# pingduino.net
KiCad netlist of a schematic drawn in EAGLE
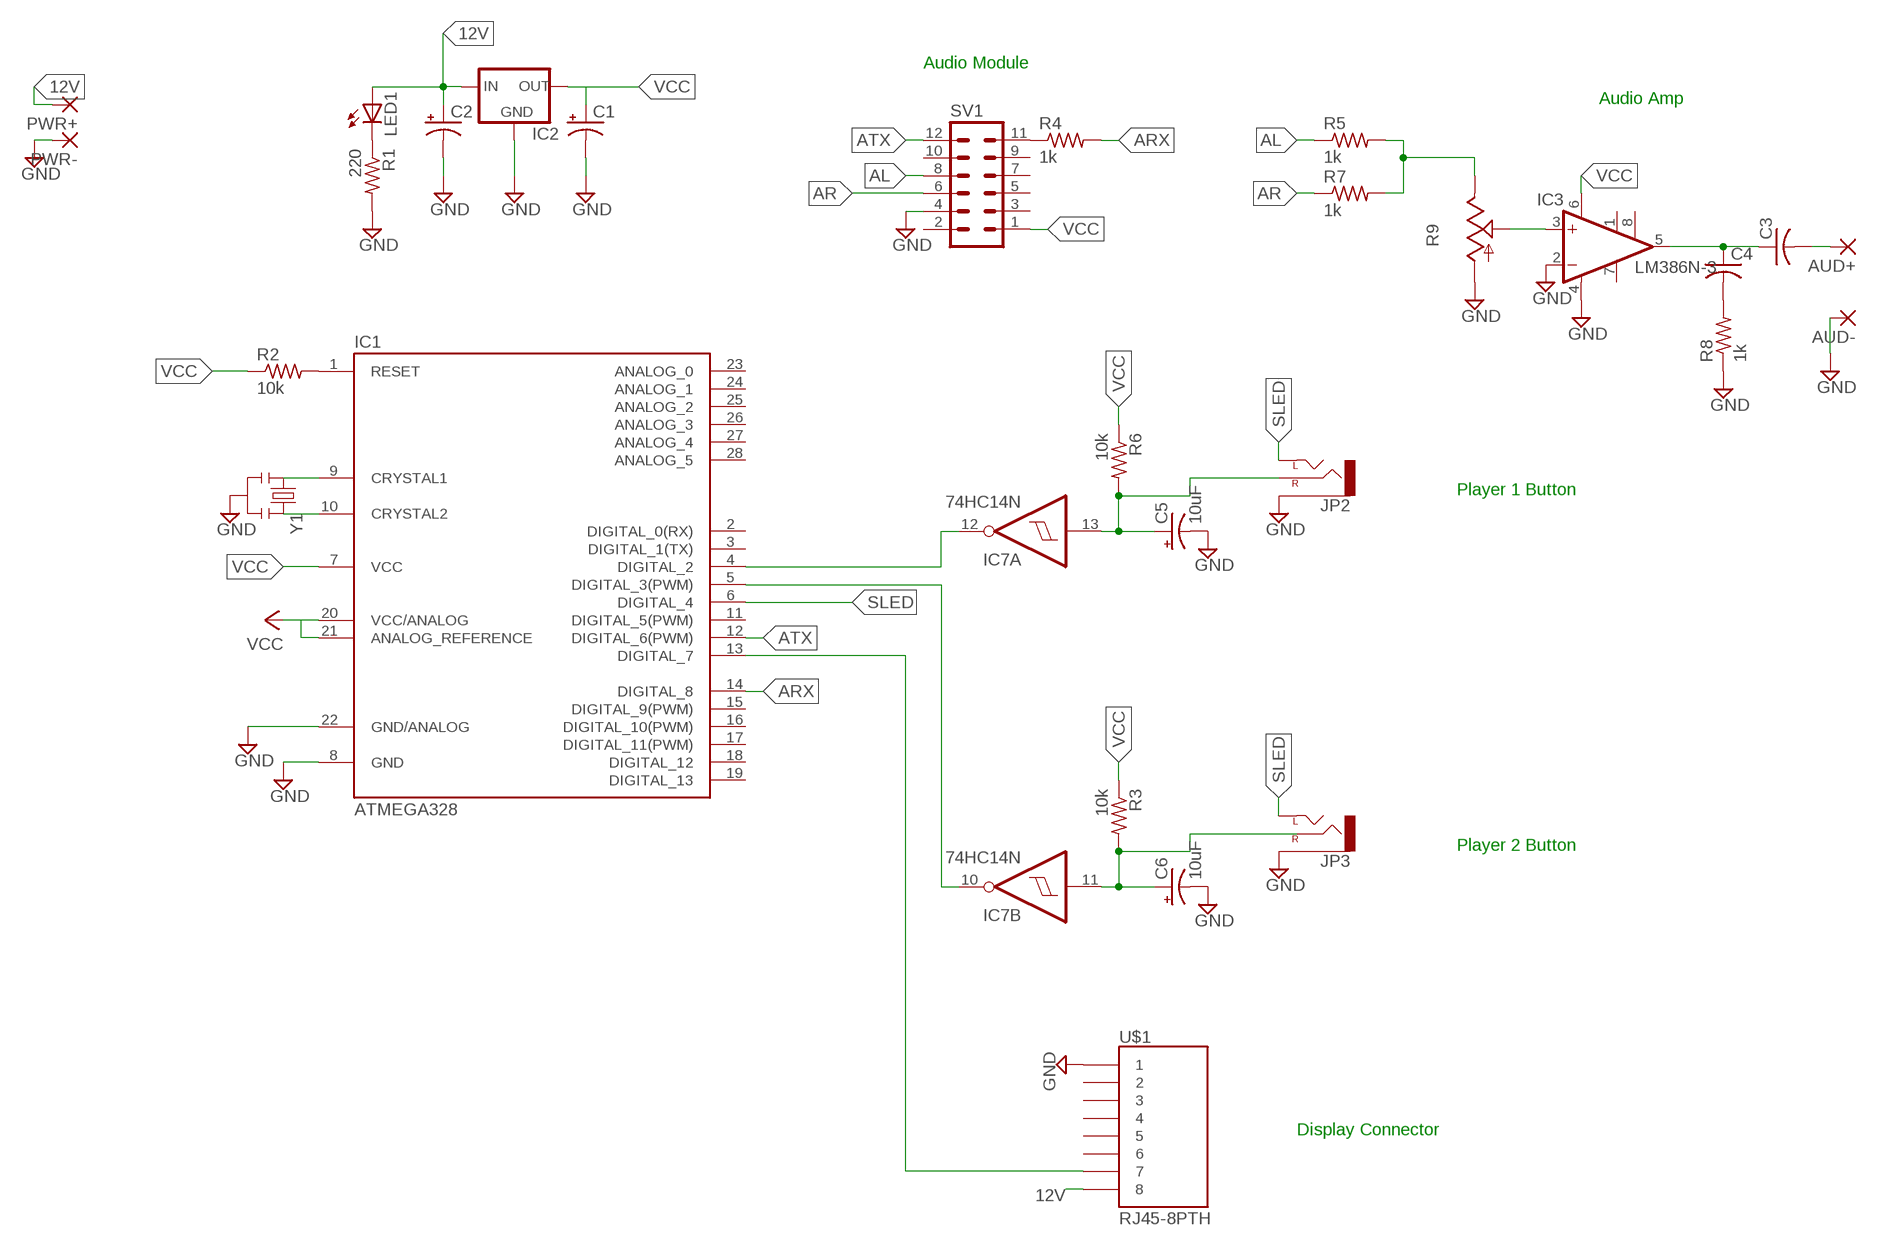
[diagram p0: schematic, sheet 1]

(export (version "E")
  (design (tool "Eeschema 10.0.6"))
  (components
    (comp (ref "AUD+")
      (value "WIREPAD2,15/1,0")
      (footprint "eagle-import:2,15_1,0")
      (libsource (lib "eagle-import") (part "WIREPAD2,15/1,0"))
    )
    (comp (ref "AUD-")
      (value "WIREPAD2,15/1,0")
      (footprint "eagle-import:2,15_1,0")
      (libsource (lib "eagle-import") (part "WIREPAD2,15/1,0"))
    )
    (comp (ref "C1")
      (value "CAP_POLPTH2")
      (footprint "eagle-import:CPOL-RADIAL-10UF-25V")
      (libsource (lib "eagle-import") (part "CAP_POLPTH2"))
    )
    (comp (ref "C2")
      (value "CAP_POLPTH2")
      (footprint "eagle-import:CPOL-RADIAL-10UF-25V")
      (libsource (lib "eagle-import") (part "CAP_POLPTH2"))
    )
    (comp (ref "C3")
      (value "C-US050-024X044")
      (footprint "eagle-import:C050-024X044")
      (libsource (lib "eagle-import") (part "C-US050-024X044"))
    )
    (comp (ref "C4")
      (value "C-US050-024X044")
      (footprint "eagle-import:C050-024X044")
      (libsource (lib "eagle-import") (part "C-US050-024X044"))
    )
    (comp (ref "C5")
      (value "10uF")
      (footprint "eagle-import:CPOL-RADIAL-10UF-25V")
      (libsource (lib "eagle-import") (part "CAP_POLPTH2"))
    )
    (comp (ref "C6")
      (value "10uF")
      (footprint "eagle-import:CPOL-RADIAL-10UF-25V")
      (libsource (lib "eagle-import") (part "CAP_POLPTH2"))
    )
    (comp (ref "IC1")
      (value "ATMEGA328")
      (footprint "eagle-import:DIL28-3")
      (libsource (lib "eagle-import") (part "ATMEGA168-PU"))
    )
    (comp (ref "IC2")
      (value "V_REG_78XX-TO-220")
      (footprint "eagle-import:TO-220-ALT")
      (libsource (lib "eagle-import") (part "V_REG_78XX-TO-220"))
    )
    (comp (ref "IC3")
      (value "LM386N-3")
      (footprint "eagle-import:DIL08")
      (libsource (lib "eagle-import") (part "LM386?-N3"))
    )
    (comp (ref "IC7")
      (value "74HC14N")
      (footprint "eagle-import:DIL14")
      (libsource (lib "eagle-import") (part "7414NHC"))
    )
    (comp (ref "JP2")
      (value "AUDIO-JACKPTH")
      (footprint "eagle-import:AUDIO-JACK")
      (libsource (lib "eagle-import") (part "AUDIO-JACKPTH"))
    )
    (comp (ref "JP3")
      (value "AUDIO-JACKPTH")
      (footprint "eagle-import:AUDIO-JACK")
      (libsource (lib "eagle-import") (part "AUDIO-JACKPTH"))
    )
    (comp (ref "LED1")
      (value "LED3MM")
      (footprint "eagle-import:LED3MM")
      (libsource (lib "eagle-import") (part "LED3MM"))
    )
    (comp (ref "PWR+")
      (value "WIREPAD2,15/1,0")
      (footprint "eagle-import:2,15_1,0")
      (libsource (lib "eagle-import") (part "WIREPAD2,15/1,0"))
    )
    (comp (ref "PWR-")
      (value "WIREPAD2,15/1,0")
      (footprint "eagle-import:2,15_1,0")
      (libsource (lib "eagle-import") (part "WIREPAD2,15/1,0"))
    )
    (comp (ref "R1")
      (value "220")
      (footprint "eagle-import:0204_7")
      (libsource (lib "eagle-import") (part "R-US_0204/7"))
    )
    (comp (ref "R2")
      (value "10k")
      (footprint "eagle-import:0204_7")
      (libsource (lib "eagle-import") (part "R-US_0204/7"))
    )
    (comp (ref "R3")
      (value "10k")
      (footprint "eagle-import:0204_7")
      (libsource (lib "eagle-import") (part "R-US_0204/7"))
    )
    (comp (ref "R4")
      (value "1k")
      (footprint "eagle-import:0204_7")
      (libsource (lib "eagle-import") (part "R-US_0204/7"))
    )
    (comp (ref "R5")
      (value "1k")
      (footprint "eagle-import:0204_7")
      (libsource (lib "eagle-import") (part "R-US_0204/7"))
    )
    (comp (ref "R6")
      (value "10k")
      (footprint "eagle-import:0204_7")
      (libsource (lib "eagle-import") (part "R-US_0204/7"))
    )
    (comp (ref "R7")
      (value "1k")
      (footprint "eagle-import:0204_7")
      (libsource (lib "eagle-import") (part "R-US_0204/7"))
    )
    (comp (ref "R8")
      (value "1k")
      (footprint "eagle-import:0204_7")
      (libsource (lib "eagle-import") (part "R-US_0204/7"))
    )
    (comp (ref "R9")
      (value "TRIM_US-B25U")
      (footprint "eagle-import:B25U")
      (libsource (lib "eagle-import") (part "TRIM_US-B25U"))
    )
    (comp (ref "SV1")
      (value "MA06-2")
      (footprint "eagle-import:MA06-2")
      (libsource (lib "eagle-import") (part "MA06-2"))
    )
    (comp (ref "U$1")
      (value "RJ45-8PTH")
      (footprint "eagle-import:RJ45-8")
      (libsource (lib "eagle-import") (part "RJ45-8PTH"))
    )
    (comp (ref "Y1")
      (value "RESONATORPTH")
      (footprint "eagle-import:RESONATOR-PTH")
      (libsource (lib "eagle-import") (part "RESONATORPTH"))
    )
  )
  (nets
    (net (code "1") (name "12V") (class "Default")
      (node (ref "C2") (pin "1") (pinfunction "+_1") (pintype "passive"))
      (node (ref "IC2") (pin "IN") (pinfunction "IN_IN") (pintype "input"))
      (node (ref "LED1") (pin "A") (pinfunction "A_A") (pintype "passive"))
      (node (ref "PWR+") (pin "1") (pinfunction "P_1") (pintype "passive"))
      (node (ref "U$1") (pin "8") (pinfunction "8_8") (pintype "bidirectional"))
    )
    (net (code "2") (name "AL") (class "Default")
      (node (ref "R5") (pin "1") (pinfunction "1_1") (pintype "passive"))
      (node (ref "SV1") (pin "8") (pinfunction "8_8") (pintype "passive"))
    )
    (net (code "3") (name "AR") (class "Default")
      (node (ref "R7") (pin "1") (pinfunction "1_1") (pintype "passive"))
      (node (ref "SV1") (pin "6") (pinfunction "6_6") (pintype "passive"))
    )
    (net (code "4") (name "ARX") (class "Default")
      (node (ref "IC1") (pin "13") (pinfunction "DIGITAL_7_13") (pintype "bidirectional"))
      (node (ref "IC1") (pin "14") (pinfunction "DIGITAL_8_14") (pintype "bidirectional"))
      (node (ref "R4") (pin "2") (pinfunction "2_2") (pintype "passive"))
      (node (ref "U$1") (pin "7") (pinfunction "7_7") (pintype "bidirectional"))
    )
    (net (code "5") (name "ATX") (class "Default")
      (node (ref "IC1") (pin "12") (pinfunction "DIGITAL_6(PWM)_12") (pintype "bidirectional"))
      (node (ref "SV1") (pin "12") (pinfunction "12_12") (pintype "passive"))
    )
    (net (code "6") (name "GND") (class "Default")
      (node (ref "AUD-") (pin "1") (pinfunction "P_1") (pintype "passive"))
      (node (ref "C1") (pin "2") (pinfunction "-_2") (pintype "passive"))
      (node (ref "C2") (pin "2") (pinfunction "-_2") (pintype "passive"))
      (node (ref "C5") (pin "2") (pinfunction "-_2") (pintype "passive"))
      (node (ref "C6") (pin "2") (pinfunction "-_2") (pintype "passive"))
      (node (ref "IC1") (pin "22") (pinfunction "GND/ANALOG_22") (pintype "power_in"))
      (node (ref "IC1") (pin "8") (pinfunction "GND_8") (pintype "power_in"))
      (node (ref "IC2") (pin "GND") (pinfunction "GND_GND") (pintype "input"))
      (node (ref "IC3") (pin "2") (pinfunction "-IN_2") (pintype "input"))
      (node (ref "IC3") (pin "4") (pinfunction "GND_4") (pintype "power_in"))
      (node (ref "JP2") (pin "SLEEVE") (pinfunction "SLEEVE_SLEEVE") (pintype "bidirectional"))
      (node (ref "JP3") (pin "SLEEVE") (pinfunction "SLEEVE_SLEEVE") (pintype "bidirectional"))
      (node (ref "PWR-") (pin "1") (pinfunction "P_1") (pintype "passive"))
      (node (ref "R1") (pin "2") (pinfunction "2_2") (pintype "passive"))
      (node (ref "R8") (pin "1") (pinfunction "1_1") (pintype "passive"))
      (node (ref "R9") (pin "A") (pinfunction "A_A") (pintype "passive"))
      (node (ref "SV1") (pin "4") (pinfunction "4_4") (pintype "passive"))
      (node (ref "U$1") (pin "1") (pinfunction "1_1") (pintype "bidirectional"))
      (node (ref "Y1") (pin "2") (pinfunction "2_2") (pintype "passive"))
    )
    (net (code "7") (name "Net-(AUD+-P)") (class "Default")
      (node (ref "AUD+") (pin "1") (pinfunction "P_1") (pintype "passive"))
      (node (ref "C3") (pin "2") (pinfunction "2_2") (pintype "passive"))
    )
    (net (code "8") (name "Net-(C4-Pad2)") (class "Default")
      (node (ref "C4") (pin "2") (pinfunction "2_2") (pintype "passive"))
      (node (ref "R8") (pin "2") (pinfunction "2_2") (pintype "passive"))
    )
    (net (code "9") (name "Net-(C5-+)") (class "Default")
      (node (ref "C5") (pin "1") (pinfunction "+_1") (pintype "passive"))
      (node (ref "IC7") (pin "13") (pinfunction "I_13") (pintype "input"))
      (node (ref "JP2") (pin "RING") (pinfunction "RIGHT_RING") (pintype "bidirectional"))
      (node (ref "R6") (pin "2") (pinfunction "2_2") (pintype "passive"))
    )
    (net (code "10") (name "Net-(C6-+)") (class "Default")
      (node (ref "C6") (pin "1") (pinfunction "+_1") (pintype "passive"))
      (node (ref "IC7") (pin "11") (pinfunction "I_11") (pintype "input"))
      (node (ref "R3") (pin "2") (pinfunction "2_2") (pintype "passive"))
    )
    (net (code "11") (name "Net-(IC1-CRYSTAL1)") (class "Default")
      (node (ref "IC1") (pin "9") (pinfunction "CRYSTAL1_9") (pintype "bidirectional"))
      (node (ref "Y1") (pin "1") (pinfunction "1_1") (pintype "passive"))
    )
    (net (code "12") (name "Net-(IC1-CRYSTAL2)") (class "Default")
      (node (ref "IC1") (pin "10") (pinfunction "CRYSTAL2_10") (pintype "bidirectional"))
      (node (ref "Y1") (pin "3") (pinfunction "3_3") (pintype "passive"))
    )
    (net (code "13") (name "Net-(IC1-DIGITAL_2)") (class "Default")
      (node (ref "IC1") (pin "4") (pinfunction "DIGITAL_2_4") (pintype "bidirectional"))
      (node (ref "IC7") (pin "12") (pinfunction "O_12") (pintype "output"))
    )
    (net (code "14") (name "Net-(IC1-DIGITAL_3(PWM))") (class "Default")
      (node (ref "IC1") (pin "5") (pinfunction "DIGITAL_3(PWM)_5") (pintype "bidirectional"))
      (node (ref "IC7") (pin "10") (pinfunction "O_10") (pintype "output"))
    )
    (net (code "15") (name "Net-(IC1-RESET)") (class "Default")
      (node (ref "IC1") (pin "1") (pinfunction "RESET_1") (pintype "bidirectional"))
      (node (ref "R2") (pin "2") (pinfunction "2_2") (pintype "passive"))
    )
    (net (code "16") (name "Net-(IC3-+IN)") (class "Default")
      (node (ref "IC3") (pin "3") (pinfunction "+IN_3") (pintype "input"))
      (node (ref "R9") (pin "S") (pinfunction "S_S") (pintype "passive"))
    )
    (net (code "17") (name "Net-(IC3-OUT)") (class "Default")
      (node (ref "C3") (pin "1") (pinfunction "1_1") (pintype "passive"))
      (node (ref "C4") (pin "1") (pinfunction "1_1") (pintype "passive"))
      (node (ref "IC3") (pin "5") (pinfunction "OUT_5") (pintype "output"))
    )
    (net (code "18") (name "Net-(LED1-C)") (class "Default")
      (node (ref "LED1") (pin "K") (pinfunction "C_K") (pintype "passive"))
      (node (ref "R1") (pin "1") (pinfunction "1_1") (pintype "passive"))
    )
    (net (code "19") (name "Net-(R4-Pad1)") (class "Default")
      (node (ref "R4") (pin "1") (pinfunction "1_1") (pintype "passive"))
      (node (ref "SV1") (pin "11") (pinfunction "11_11") (pintype "passive"))
    )
    (net (code "20") (name "Net-(R5-Pad2)") (class "Default")
      (node (ref "R5") (pin "2") (pinfunction "2_2") (pintype "passive"))
      (node (ref "R7") (pin "2") (pinfunction "2_2") (pintype "passive"))
      (node (ref "R9") (pin "E") (pinfunction "E_E") (pintype "passive"))
    )
    (net (code "21") (name "SLED") (class "Default")
      (node (ref "IC1") (pin "6") (pinfunction "DIGITAL_4_6") (pintype "bidirectional"))
      (node (ref "JP2") (pin "TIP") (pinfunction "LEFT_TIP") (pintype "bidirectional"))
      (node (ref "JP3") (pin "TIP") (pinfunction "LEFT_TIP") (pintype "bidirectional"))
    )
    (net (code "22") (name "VCC") (class "Default")
      (node (ref "C1") (pin "1") (pinfunction "+_1") (pintype "passive"))
      (node (ref "IC1") (pin "20") (pinfunction "VCC/ANALOG_20") (pintype "passive"))
      (node (ref "IC1") (pin "21") (pinfunction "ANALOG_REFERENCE_21") (pintype "passive"))
      (node (ref "IC1") (pin "7") (pinfunction "VCC_7") (pintype "power_in"))
      (node (ref "IC2") (pin "OUT") (pinfunction "OUT_OUT") (pintype "output"))
      (node (ref "IC3") (pin "6") (pinfunction "VS_6") (pintype "power_in"))
      (node (ref "R2") (pin "1") (pinfunction "1_1") (pintype "passive"))
      (node (ref "R3") (pin "1") (pinfunction "1_1") (pintype "passive"))
      (node (ref "R6") (pin "1") (pinfunction "1_1") (pintype "passive"))
      (node (ref "SV1") (pin "1") (pinfunction "1_1") (pintype "passive"))
    )
    (net (code "23") (name "unconnected-(IC1-ANALOG_0-Pad23)") (class "Default")
      (node (ref "IC1") (pin "23") (pinfunction "ANALOG_0_23") (pintype "bidirectional"))
    )
    (net (code "24") (name "unconnected-(IC1-ANALOG_1-Pad24)") (class "Default")
      (node (ref "IC1") (pin "24") (pinfunction "ANALOG_1_24") (pintype "bidirectional"))
    )
    (net (code "25") (name "unconnected-(IC1-ANALOG_2-Pad25)") (class "Default")
      (node (ref "IC1") (pin "25") (pinfunction "ANALOG_2_25") (pintype "bidirectional"))
    )
    (net (code "26") (name "unconnected-(IC1-ANALOG_3-Pad26)") (class "Default")
      (node (ref "IC1") (pin "26") (pinfunction "ANALOG_3_26") (pintype "bidirectional"))
    )
    (net (code "27") (name "unconnected-(IC1-ANALOG_4-Pad27)") (class "Default")
      (node (ref "IC1") (pin "27") (pinfunction "ANALOG_4_27") (pintype "bidirectional"))
    )
    (net (code "28") (name "unconnected-(IC1-ANALOG_5-Pad28)") (class "Default")
      (node (ref "IC1") (pin "28") (pinfunction "ANALOG_5_28") (pintype "bidirectional"))
    )
    (net (code "29") (name "unconnected-(IC1-DIGITAL_0(RX)-Pad2)") (class "Default")
      (node (ref "IC1") (pin "2") (pinfunction "DIGITAL_0(RX)_2") (pintype "bidirectional"))
    )
    (net (code "30") (name "unconnected-(IC1-DIGITAL_1(TX)-Pad3)") (class "Default")
      (node (ref "IC1") (pin "3") (pinfunction "DIGITAL_1(TX)_3") (pintype "bidirectional"))
    )
    (net (code "31") (name "unconnected-(IC1-DIGITAL_5(PWM)-Pad11)") (class "Default")
      (node (ref "IC1") (pin "11") (pinfunction "DIGITAL_5(PWM)_11") (pintype "bidirectional"))
    )
    (net (code "32") (name "unconnected-(IC1-DIGITAL_9(PWM)-Pad15)") (class "Default")
      (node (ref "IC1") (pin "15") (pinfunction "DIGITAL_9(PWM)_15") (pintype "bidirectional"))
    )
    (net (code "33") (name "unconnected-(IC1-DIGITAL_10(PWM)-Pad16)") (class "Default")
      (node (ref "IC1") (pin "16") (pinfunction "DIGITAL_10(PWM)_16") (pintype "bidirectional"))
    )
    (net (code "34") (name "unconnected-(IC1-DIGITAL_11(PWM)-Pad17)") (class "Default")
      (node (ref "IC1") (pin "17") (pinfunction "DIGITAL_11(PWM)_17") (pintype "bidirectional"))
    )
    (net (code "35") (name "unconnected-(IC1-DIGITAL_12-Pad18)") (class "Default")
      (node (ref "IC1") (pin "18") (pinfunction "DIGITAL_12_18") (pintype "bidirectional"))
    )
    (net (code "36") (name "unconnected-(IC1-DIGITAL_13-Pad19)") (class "Default")
      (node (ref "IC1") (pin "19") (pinfunction "DIGITAL_13_19") (pintype "bidirectional"))
    )
    (net (code "37") (name "unconnected-(IC3-BYPASS-Pad7)") (class "Default")
      (node (ref "IC3") (pin "7") (pinfunction "BYPASS_7") (pintype "passive"))
    )
    (net (code "38") (name "unconnected-(IC3-GAIN-Pad1)") (class "Default")
      (node (ref "IC3") (pin "1") (pinfunction "GAIN_1") (pintype "passive"))
    )
    (net (code "39") (name "unconnected-(IC3-GAIN-Pad8)") (class "Default")
      (node (ref "IC3") (pin "8") (pinfunction "GAIN_8") (pintype "passive"))
    )
    (net (code "40") (name "unconnected-(JP3-RIGHT-PadRING)") (class "Default")
      (node (ref "JP3") (pin "RING") (pinfunction "RIGHT_RING") (pintype "bidirectional"))
    )
    (net (code "41") (name "unconnected-(SV1-Pad2)") (class "Default")
      (node (ref "SV1") (pin "2") (pinfunction "2_2") (pintype "passive"))
    )
    (net (code "42") (name "unconnected-(SV1-Pad3)") (class "Default")
      (node (ref "SV1") (pin "3") (pinfunction "3_3") (pintype "passive"))
    )
    (net (code "43") (name "unconnected-(SV1-Pad5)") (class "Default")
      (node (ref "SV1") (pin "5") (pinfunction "5_5") (pintype "passive"))
    )
    (net (code "44") (name "unconnected-(SV1-Pad7)") (class "Default")
      (node (ref "SV1") (pin "7") (pinfunction "7_7") (pintype "passive"))
    )
    (net (code "45") (name "unconnected-(SV1-Pad9)") (class "Default")
      (node (ref "SV1") (pin "9") (pinfunction "9_9") (pintype "passive"))
    )
    (net (code "46") (name "unconnected-(SV1-Pad10)") (class "Default")
      (node (ref "SV1") (pin "10") (pinfunction "10_10") (pintype "passive"))
    )
    (net (code "47") (name "unconnected-(U$1-Pad2)") (class "Default")
      (node (ref "U$1") (pin "2") (pinfunction "2_2") (pintype "bidirectional"))
    )
    (net (code "48") (name "unconnected-(U$1-Pad3)") (class "Default")
      (node (ref "U$1") (pin "3") (pinfunction "3_3") (pintype "bidirectional"))
    )
    (net (code "49") (name "unconnected-(U$1-Pad4)") (class "Default")
      (node (ref "U$1") (pin "4") (pinfunction "4_4") (pintype "bidirectional"))
    )
    (net (code "50") (name "unconnected-(U$1-Pad5)") (class "Default")
      (node (ref "U$1") (pin "5") (pinfunction "5_5") (pintype "bidirectional"))
    )
    (net (code "51") (name "unconnected-(U$1-Pad6)") (class "Default")
      (node (ref "U$1") (pin "6") (pinfunction "6_6") (pintype "bidirectional"))
    )
  )
)
